# Power4x4r2.net
KiCad netlist of a schematic drawn in EAGLE
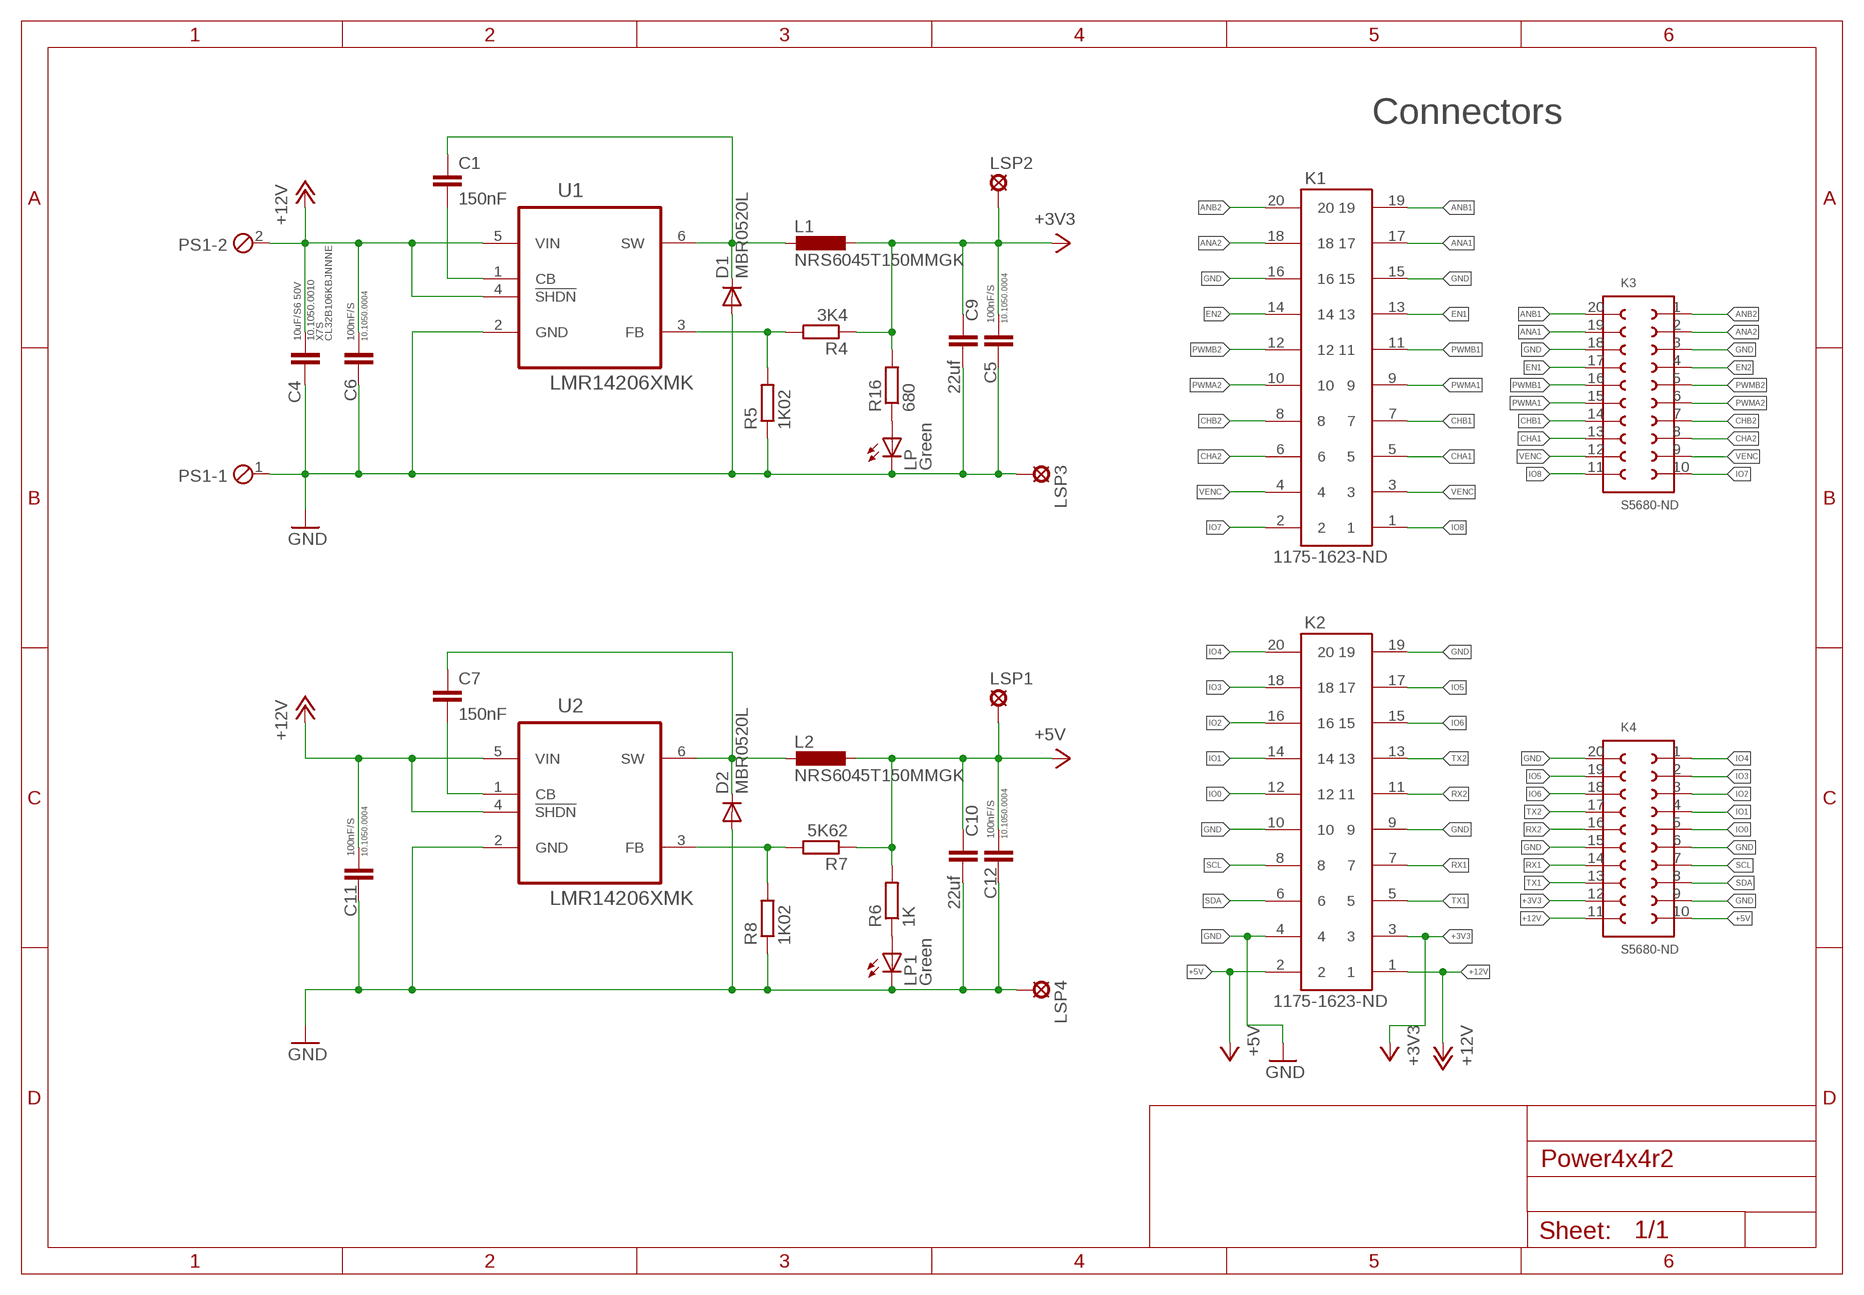
[diagram p0: schematic, sheet 1]

(export (version "E")
  (design (tool "Eeschema 10.0.6"))
  (components
    (comp (ref "C1")
      (value "150nF")
      (footprint "eagle-import:C0805K")
      (libsource (lib "eagle-import") (part "C-EUC0805K"))
    )
    (comp (ref "C4")
      (value "10uF/S6 50V")
      (footprint "eagle-import:C3225")
      (fields
        (field (name "CODE") "CL32B106KBJNNNE")
        (field (name "KATODO") "10.1050.0010")
        (field (name "TEMPERATURE") "X7S")
      )
      (libsource (lib "eagle-import") (part "C-EUC3225"))
    )
    (comp (ref "C5")
      (value "100nF/S")
      (footprint "eagle-import:C0805")
      (fields (field (name "KATODO") "10.1050.0004"))
      (libsource (lib "eagle-import") (part "C-EUC0805"))
    )
    (comp (ref "C6")
      (value "100nF/S")
      (footprint "eagle-import:C0805")
      (fields (field (name "KATODO") "10.1050.0004"))
      (libsource (lib "eagle-import") (part "C-EUC0805"))
    )
    (comp (ref "C7")
      (value "150nF")
      (footprint "eagle-import:C0805K")
      (libsource (lib "eagle-import") (part "C-EUC0805K"))
    )
    (comp (ref "C9")
      (value "22uf")
      (footprint "eagle-import:C1206")
      (libsource (lib "eagle-import") (part "C-EUC1206"))
    )
    (comp (ref "C10")
      (value "22uf")
      (footprint "eagle-import:C1206")
      (libsource (lib "eagle-import") (part "C-EUC1206"))
    )
    (comp (ref "C11")
      (value "100nF/S")
      (footprint "eagle-import:C0805")
      (fields (field (name "KATODO") "10.1050.0004"))
      (libsource (lib "eagle-import") (part "C-EUC0805"))
    )
    (comp (ref "C12")
      (value "100nF/S")
      (footprint "eagle-import:C0805")
      (fields (field (name "KATODO") "10.1050.0004"))
      (libsource (lib "eagle-import") (part "C-EUC0805"))
    )
    (comp (ref "D1")
      (value "MBR0520L")
      (footprint "eagle-import:SOD123")
      (libsource (lib "eagle-import") (part "DIODE-SOD123"))
    )
    (comp (ref "D2")
      (value "MBR0520L")
      (footprint "eagle-import:SOD123")
      (libsource (lib "eagle-import") (part "DIODE-SOD123"))
    )
    (comp (ref "K1")
      (value "1175-1623-ND")
      (footprint "eagle-import:612X2020621")
      (libsource (lib "eagle-import") (part "612X2020621"))
    )
    (comp (ref "K2")
      (value "1175-1623-ND")
      (footprint "eagle-import:612X2020621")
      (libsource (lib "eagle-import") (part "612X2020621"))
    )
    (comp (ref "K3")
      (value "S5680-ND")
      (footprint "eagle-import:61002021821")
      (libsource (lib "eagle-import") (part "61002021821"))
    )
    (comp (ref "K4")
      (value "S5680-ND")
      (footprint "eagle-import:61002021821")
      (libsource (lib "eagle-import") (part "61002021821"))
    )
    (comp (ref "L1")
      (value "NRS6045T150MMGK")
      (footprint "eagle-import:POWER-CHOKE_WE-TPC")
      (libsource (lib "eagle-import") (part "L-EUWE-TPC"))
    )
    (comp (ref "L2")
      (value "NRS6045T150MMGK")
      (footprint "eagle-import:POWER-CHOKE_WE-TPC")
      (libsource (lib "eagle-import") (part "L-EUWE-TPC"))
    )
    (comp (ref "LP")
      (value "Green")
      (footprint "eagle-import:CHIPLED_0805")
      (libsource (lib "eagle-import") (part "LEDCHIPLED_0805"))
    )
    (comp (ref "LP1")
      (value "Green")
      (footprint "eagle-import:CHIPLED_0805")
      (libsource (lib "eagle-import") (part "LEDCHIPLED_0805"))
    )
    (comp (ref "LSP1")
      (value "LSP10")
      (footprint "eagle-import:LSP10")
      (libsource (lib "eagle-import") (part "LSP10"))
    )
    (comp (ref "LSP2")
      (value "LSP10")
      (footprint "eagle-import:LSP10")
      (libsource (lib "eagle-import") (part "LSP10"))
    )
    (comp (ref "LSP3")
      (value "LSP10")
      (footprint "eagle-import:LSP10")
      (libsource (lib "eagle-import") (part "LSP10"))
    )
    (comp (ref "LSP4")
      (value "LSP10")
      (footprint "eagle-import:LSP10")
      (libsource (lib "eagle-import") (part "LSP10"))
    )
    (comp (ref "PS1")
      (value "MPT2")
      (footprint "eagle-import:2POL254")
      (libsource (lib "eagle-import") (part "MPT2"))
    )
    (comp (ref "R4")
      (value "3K4")
      (footprint "eagle-import:R0805")
      (libsource (lib "eagle-import") (part "R-EU_R0805"))
    )
    (comp (ref "R5")
      (value "1K02")
      (footprint "eagle-import:R0805")
      (libsource (lib "eagle-import") (part "R-EU_R0805"))
    )
    (comp (ref "R6")
      (value "1K")
      (footprint "eagle-import:R0603")
      (libsource (lib "eagle-import") (part "R-EU_R0603"))
    )
    (comp (ref "R7")
      (value "5K62")
      (footprint "eagle-import:R0805")
      (libsource (lib "eagle-import") (part "R-EU_R0805"))
    )
    (comp (ref "R8")
      (value "1K02")
      (footprint "eagle-import:R0805")
      (libsource (lib "eagle-import") (part "R-EU_R0805"))
    )
    (comp (ref "R16")
      (value "680")
      (footprint "eagle-import:R0603")
      (libsource (lib "eagle-import") (part "R-EU_R0603"))
    )
    (comp (ref "U1")
      (value "LMR14206XMK")
      (footprint "eagle-import:SOT95P280X110-6N")
      (libsource (lib "eagle-import") (part "LMR14206XMK"))
    )
    (comp (ref "U2")
      (value "LMR14206XMK")
      (footprint "eagle-import:SOT95P280X110-6N")
      (libsource (lib "eagle-import") (part "LMR14206XMK"))
    )
  )
  (nets
    (net (code "1") (name "+3V3") (class "Default")
      (node (ref "C5") (pin "2") (pinfunction "2_2") (pintype "passive"))
      (node (ref "C9") (pin "1") (pinfunction "1_1") (pintype "passive"))
      (node (ref "K2") (pin "3") (pinfunction "3_3") (pintype "passive"))
      (node (ref "K4") (pin "12") (pinfunction "12_12") (pintype "passive"))
      (node (ref "L1") (pin "1") (pinfunction "1_1") (pintype "passive"))
      (node (ref "LSP2") (pin "MP") (pinfunction "MP_MP") (pintype "passive"))
      (node (ref "R16") (pin "2") (pinfunction "2_2") (pintype "passive"))
      (node (ref "R4") (pin "1") (pinfunction "1_1") (pintype "passive"))
    )
    (net (code "2") (name "+5V") (class "Default")
      (node (ref "C10") (pin "1") (pinfunction "1_1") (pintype "passive"))
      (node (ref "C12") (pin "2") (pinfunction "2_2") (pintype "passive"))
      (node (ref "K2") (pin "2") (pinfunction "2_2") (pintype "passive"))
      (node (ref "K4") (pin "10") (pinfunction "10_10") (pintype "passive"))
      (node (ref "L2") (pin "1") (pinfunction "1_1") (pintype "passive"))
      (node (ref "LSP1") (pin "MP") (pinfunction "MP_MP") (pintype "passive"))
      (node (ref "R6") (pin "2") (pinfunction "2_2") (pintype "passive"))
      (node (ref "R7") (pin "1") (pinfunction "1_1") (pintype "passive"))
    )
    (net (code "3") (name "+12V") (class "Default")
      (node (ref "C11") (pin "2") (pinfunction "2_2") (pintype "passive"))
      (node (ref "C4") (pin "1") (pinfunction "1_1") (pintype "passive"))
      (node (ref "C6") (pin "2") (pinfunction "2_2") (pintype "passive"))
      (node (ref "K2") (pin "1") (pinfunction "1_1") (pintype "passive"))
      (node (ref "K4") (pin "11") (pinfunction "11_11") (pintype "passive"))
      (node (ref "PS1") (pin "2") (pinfunction "1_2") (pintype "passive"))
      (node (ref "U1") (pin "4") (pinfunction "~{SHDN}_4") (pintype "input"))
      (node (ref "U1") (pin "5") (pinfunction "VIN_5") (pintype "power_in"))
      (node (ref "U2") (pin "4") (pinfunction "~{SHDN}_4") (pintype "input"))
      (node (ref "U2") (pin "5") (pinfunction "VIN_5") (pintype "power_in"))
    )
    (net (code "4") (name "ANA1") (class "Default")
      (node (ref "K1") (pin "17") (pinfunction "17_17") (pintype "passive"))
      (node (ref "K3") (pin "19") (pinfunction "19_19") (pintype "passive"))
    )
    (net (code "5") (name "ANA2") (class "Default")
      (node (ref "K1") (pin "18") (pinfunction "18_18") (pintype "passive"))
      (node (ref "K3") (pin "2") (pinfunction "2_2") (pintype "passive"))
    )
    (net (code "6") (name "ANB1") (class "Default")
      (node (ref "K1") (pin "19") (pinfunction "19_19") (pintype "passive"))
      (node (ref "K3") (pin "20") (pinfunction "20_20") (pintype "passive"))
    )
    (net (code "7") (name "ANB2") (class "Default")
      (node (ref "K1") (pin "20") (pinfunction "20_20") (pintype "passive"))
      (node (ref "K3") (pin "1") (pinfunction "1_1") (pintype "passive"))
    )
    (net (code "8") (name "CHA1") (class "Default")
      (node (ref "K1") (pin "5") (pinfunction "5_5") (pintype "passive"))
      (node (ref "K3") (pin "13") (pinfunction "13_13") (pintype "passive"))
    )
    (net (code "9") (name "CHA2") (class "Default")
      (node (ref "K1") (pin "6") (pinfunction "6_6") (pintype "passive"))
      (node (ref "K3") (pin "8") (pinfunction "8_8") (pintype "passive"))
    )
    (net (code "10") (name "CHB1") (class "Default")
      (node (ref "K1") (pin "7") (pinfunction "7_7") (pintype "passive"))
      (node (ref "K3") (pin "14") (pinfunction "14_14") (pintype "passive"))
    )
    (net (code "11") (name "CHB2") (class "Default")
      (node (ref "K1") (pin "8") (pinfunction "8_8") (pintype "passive"))
      (node (ref "K3") (pin "7") (pinfunction "7_7") (pintype "passive"))
    )
    (net (code "12") (name "EN1") (class "Default")
      (node (ref "K1") (pin "13") (pinfunction "13_13") (pintype "passive"))
      (node (ref "K3") (pin "17") (pinfunction "17_17") (pintype "passive"))
    )
    (net (code "13") (name "EN2") (class "Default")
      (node (ref "K1") (pin "14") (pinfunction "14_14") (pintype "passive"))
      (node (ref "K3") (pin "4") (pinfunction "4_4") (pintype "passive"))
    )
    (net (code "14") (name "GND") (class "Default")
      (node (ref "C10") (pin "2") (pinfunction "2_2") (pintype "passive"))
      (node (ref "C11") (pin "1") (pinfunction "1_1") (pintype "passive"))
      (node (ref "C12") (pin "1") (pinfunction "1_1") (pintype "passive"))
      (node (ref "C4") (pin "2") (pinfunction "2_2") (pintype "passive"))
      (node (ref "C5") (pin "1") (pinfunction "1_1") (pintype "passive"))
      (node (ref "C6") (pin "1") (pinfunction "1_1") (pintype "passive"))
      (node (ref "C9") (pin "2") (pinfunction "2_2") (pintype "passive"))
      (node (ref "D1") (pin "A") (pinfunction "A_A") (pintype "passive"))
      (node (ref "D2") (pin "A") (pinfunction "A_A") (pintype "passive"))
      (node (ref "K1") (pin "15") (pinfunction "15_15") (pintype "passive"))
      (node (ref "K1") (pin "16") (pinfunction "16_16") (pintype "passive"))
      (node (ref "K2") (pin "10") (pinfunction "10_10") (pintype "passive"))
      (node (ref "K2") (pin "19") (pinfunction "19_19") (pintype "passive"))
      (node (ref "K2") (pin "4") (pinfunction "4_4") (pintype "passive"))
      (node (ref "K2") (pin "9") (pinfunction "9_9") (pintype "passive"))
      (node (ref "K3") (pin "18") (pinfunction "18_18") (pintype "passive"))
      (node (ref "K3") (pin "3") (pinfunction "3_3") (pintype "passive"))
      (node (ref "K4") (pin "15") (pinfunction "15_15") (pintype "passive"))
      (node (ref "K4") (pin "20") (pinfunction "20_20") (pintype "passive"))
      (node (ref "K4") (pin "6") (pinfunction "6_6") (pintype "passive"))
      (node (ref "K4") (pin "9") (pinfunction "9_9") (pintype "passive"))
      (node (ref "LP") (pin "C") (pinfunction "C_C") (pintype "passive"))
      (node (ref "LP1") (pin "C") (pinfunction "C_C") (pintype "passive"))
      (node (ref "LSP3") (pin "MP") (pinfunction "MP_MP") (pintype "passive"))
      (node (ref "LSP4") (pin "MP") (pinfunction "MP_MP") (pintype "passive"))
      (node (ref "PS1") (pin "1") (pinfunction "1_1") (pintype "passive"))
      (node (ref "R5") (pin "1") (pinfunction "1_1") (pintype "passive"))
      (node (ref "R8") (pin "1") (pinfunction "1_1") (pintype "passive"))
      (node (ref "U1") (pin "2") (pinfunction "GND_2") (pintype "passive"))
      (node (ref "U2") (pin "2") (pinfunction "GND_2") (pintype "passive"))
    )
    (net (code "15") (name "IO0") (class "Default")
      (node (ref "K2") (pin "12") (pinfunction "12_12") (pintype "passive"))
      (node (ref "K4") (pin "5") (pinfunction "5_5") (pintype "passive"))
    )
    (net (code "16") (name "IO1") (class "Default")
      (node (ref "K2") (pin "14") (pinfunction "14_14") (pintype "passive"))
      (node (ref "K4") (pin "4") (pinfunction "4_4") (pintype "passive"))
    )
    (net (code "17") (name "IO2") (class "Default")
      (node (ref "K2") (pin "16") (pinfunction "16_16") (pintype "passive"))
      (node (ref "K4") (pin "3") (pinfunction "3_3") (pintype "passive"))
    )
    (net (code "18") (name "IO3") (class "Default")
      (node (ref "K2") (pin "18") (pinfunction "18_18") (pintype "passive"))
      (node (ref "K4") (pin "2") (pinfunction "2_2") (pintype "passive"))
    )
    (net (code "19") (name "IO4") (class "Default")
      (node (ref "K2") (pin "20") (pinfunction "20_20") (pintype "passive"))
      (node (ref "K4") (pin "1") (pinfunction "1_1") (pintype "passive"))
    )
    (net (code "20") (name "IO5") (class "Default")
      (node (ref "K2") (pin "17") (pinfunction "17_17") (pintype "passive"))
      (node (ref "K4") (pin "19") (pinfunction "19_19") (pintype "passive"))
    )
    (net (code "21") (name "IO6") (class "Default")
      (node (ref "K2") (pin "15") (pinfunction "15_15") (pintype "passive"))
      (node (ref "K4") (pin "18") (pinfunction "18_18") (pintype "passive"))
    )
    (net (code "22") (name "IO7") (class "Default")
      (node (ref "K1") (pin "2") (pinfunction "2_2") (pintype "passive"))
      (node (ref "K3") (pin "10") (pinfunction "10_10") (pintype "passive"))
    )
    (net (code "23") (name "IO8") (class "Default")
      (node (ref "K1") (pin "1") (pinfunction "1_1") (pintype "passive"))
      (node (ref "K3") (pin "11") (pinfunction "11_11") (pintype "passive"))
    )
    (net (code "24") (name "Net-(LP-PadA)") (class "Default")
      (node (ref "LP") (pin "A") (pinfunction "A_A") (pintype "passive"))
      (node (ref "R16") (pin "1") (pinfunction "1_1") (pintype "passive"))
    )
    (net (code "25") (name "Net-(LP1-PadA)") (class "Default")
      (node (ref "LP1") (pin "A") (pinfunction "A_A") (pintype "passive"))
      (node (ref "R6") (pin "1") (pinfunction "1_1") (pintype "passive"))
    )
    (net (code "26") (name "Net-(U1-CB)") (class "Default")
      (node (ref "C1") (pin "2") (pinfunction "2_2") (pintype "passive"))
      (node (ref "U1") (pin "1") (pinfunction "CB_1") (pintype "passive"))
    )
    (net (code "27") (name "Net-(U1-FB)") (class "Default")
      (node (ref "R4") (pin "2") (pinfunction "2_2") (pintype "passive"))
      (node (ref "R5") (pin "2") (pinfunction "2_2") (pintype "passive"))
      (node (ref "U1") (pin "3") (pinfunction "FB_3") (pintype "input"))
    )
    (net (code "28") (name "Net-(U1-SW)") (class "Default")
      (node (ref "C1") (pin "1") (pinfunction "1_1") (pintype "passive"))
      (node (ref "D1") (pin "C") (pinfunction "C_C") (pintype "passive"))
      (node (ref "L1") (pin "2") (pinfunction "2_2") (pintype "passive"))
      (node (ref "U1") (pin "6") (pinfunction "SW_6") (pintype "output"))
    )
    (net (code "29") (name "Net-(U2-CB)") (class "Default")
      (node (ref "C7") (pin "2") (pinfunction "2_2") (pintype "passive"))
      (node (ref "U2") (pin "1") (pinfunction "CB_1") (pintype "passive"))
    )
    (net (code "30") (name "Net-(U2-FB)") (class "Default")
      (node (ref "R7") (pin "2") (pinfunction "2_2") (pintype "passive"))
      (node (ref "R8") (pin "2") (pinfunction "2_2") (pintype "passive"))
      (node (ref "U2") (pin "3") (pinfunction "FB_3") (pintype "input"))
    )
    (net (code "31") (name "Net-(U2-SW)") (class "Default")
      (node (ref "C7") (pin "1") (pinfunction "1_1") (pintype "passive"))
      (node (ref "D2") (pin "C") (pinfunction "C_C") (pintype "passive"))
      (node (ref "L2") (pin "2") (pinfunction "2_2") (pintype "passive"))
      (node (ref "U2") (pin "6") (pinfunction "SW_6") (pintype "output"))
    )
    (net (code "32") (name "PWMA1") (class "Default")
      (node (ref "K1") (pin "9") (pinfunction "9_9") (pintype "passive"))
      (node (ref "K3") (pin "15") (pinfunction "15_15") (pintype "passive"))
    )
    (net (code "33") (name "PWMA2") (class "Default")
      (node (ref "K1") (pin "10") (pinfunction "10_10") (pintype "passive"))
      (node (ref "K3") (pin "6") (pinfunction "6_6") (pintype "passive"))
    )
    (net (code "34") (name "PWMB1") (class "Default")
      (node (ref "K1") (pin "11") (pinfunction "11_11") (pintype "passive"))
      (node (ref "K3") (pin "16") (pinfunction "16_16") (pintype "passive"))
    )
    (net (code "35") (name "PWMB2") (class "Default")
      (node (ref "K1") (pin "12") (pinfunction "12_12") (pintype "passive"))
      (node (ref "K3") (pin "5") (pinfunction "5_5") (pintype "passive"))
    )
    (net (code "36") (name "RX1") (class "Default")
      (node (ref "K2") (pin "7") (pinfunction "7_7") (pintype "passive"))
      (node (ref "K4") (pin "14") (pinfunction "14_14") (pintype "passive"))
    )
    (net (code "37") (name "RX2") (class "Default")
      (node (ref "K2") (pin "11") (pinfunction "11_11") (pintype "passive"))
      (node (ref "K4") (pin "16") (pinfunction "16_16") (pintype "passive"))
    )
    (net (code "38") (name "SCL") (class "Default")
      (node (ref "K2") (pin "8") (pinfunction "8_8") (pintype "passive"))
      (node (ref "K4") (pin "7") (pinfunction "7_7") (pintype "passive"))
    )
    (net (code "39") (name "SDA") (class "Default")
      (node (ref "K2") (pin "6") (pinfunction "6_6") (pintype "passive"))
      (node (ref "K4") (pin "8") (pinfunction "8_8") (pintype "passive"))
    )
    (net (code "40") (name "TX1") (class "Default")
      (node (ref "K2") (pin "5") (pinfunction "5_5") (pintype "passive"))
      (node (ref "K4") (pin "13") (pinfunction "13_13") (pintype "passive"))
    )
    (net (code "41") (name "TX2") (class "Default")
      (node (ref "K2") (pin "13") (pinfunction "13_13") (pintype "passive"))
      (node (ref "K4") (pin "17") (pinfunction "17_17") (pintype "passive"))
    )
    (net (code "42") (name "VENC") (class "Default")
      (node (ref "K1") (pin "3") (pinfunction "3_3") (pintype "passive"))
      (node (ref "K1") (pin "4") (pinfunction "4_4") (pintype "passive"))
      (node (ref "K3") (pin "12") (pinfunction "12_12") (pintype "passive"))
      (node (ref "K3") (pin "9") (pinfunction "9_9") (pintype "passive"))
    )
  )
)
